# TeensyBreakoutBoard.net
KiCad netlist of a schematic drawn in EAGLE
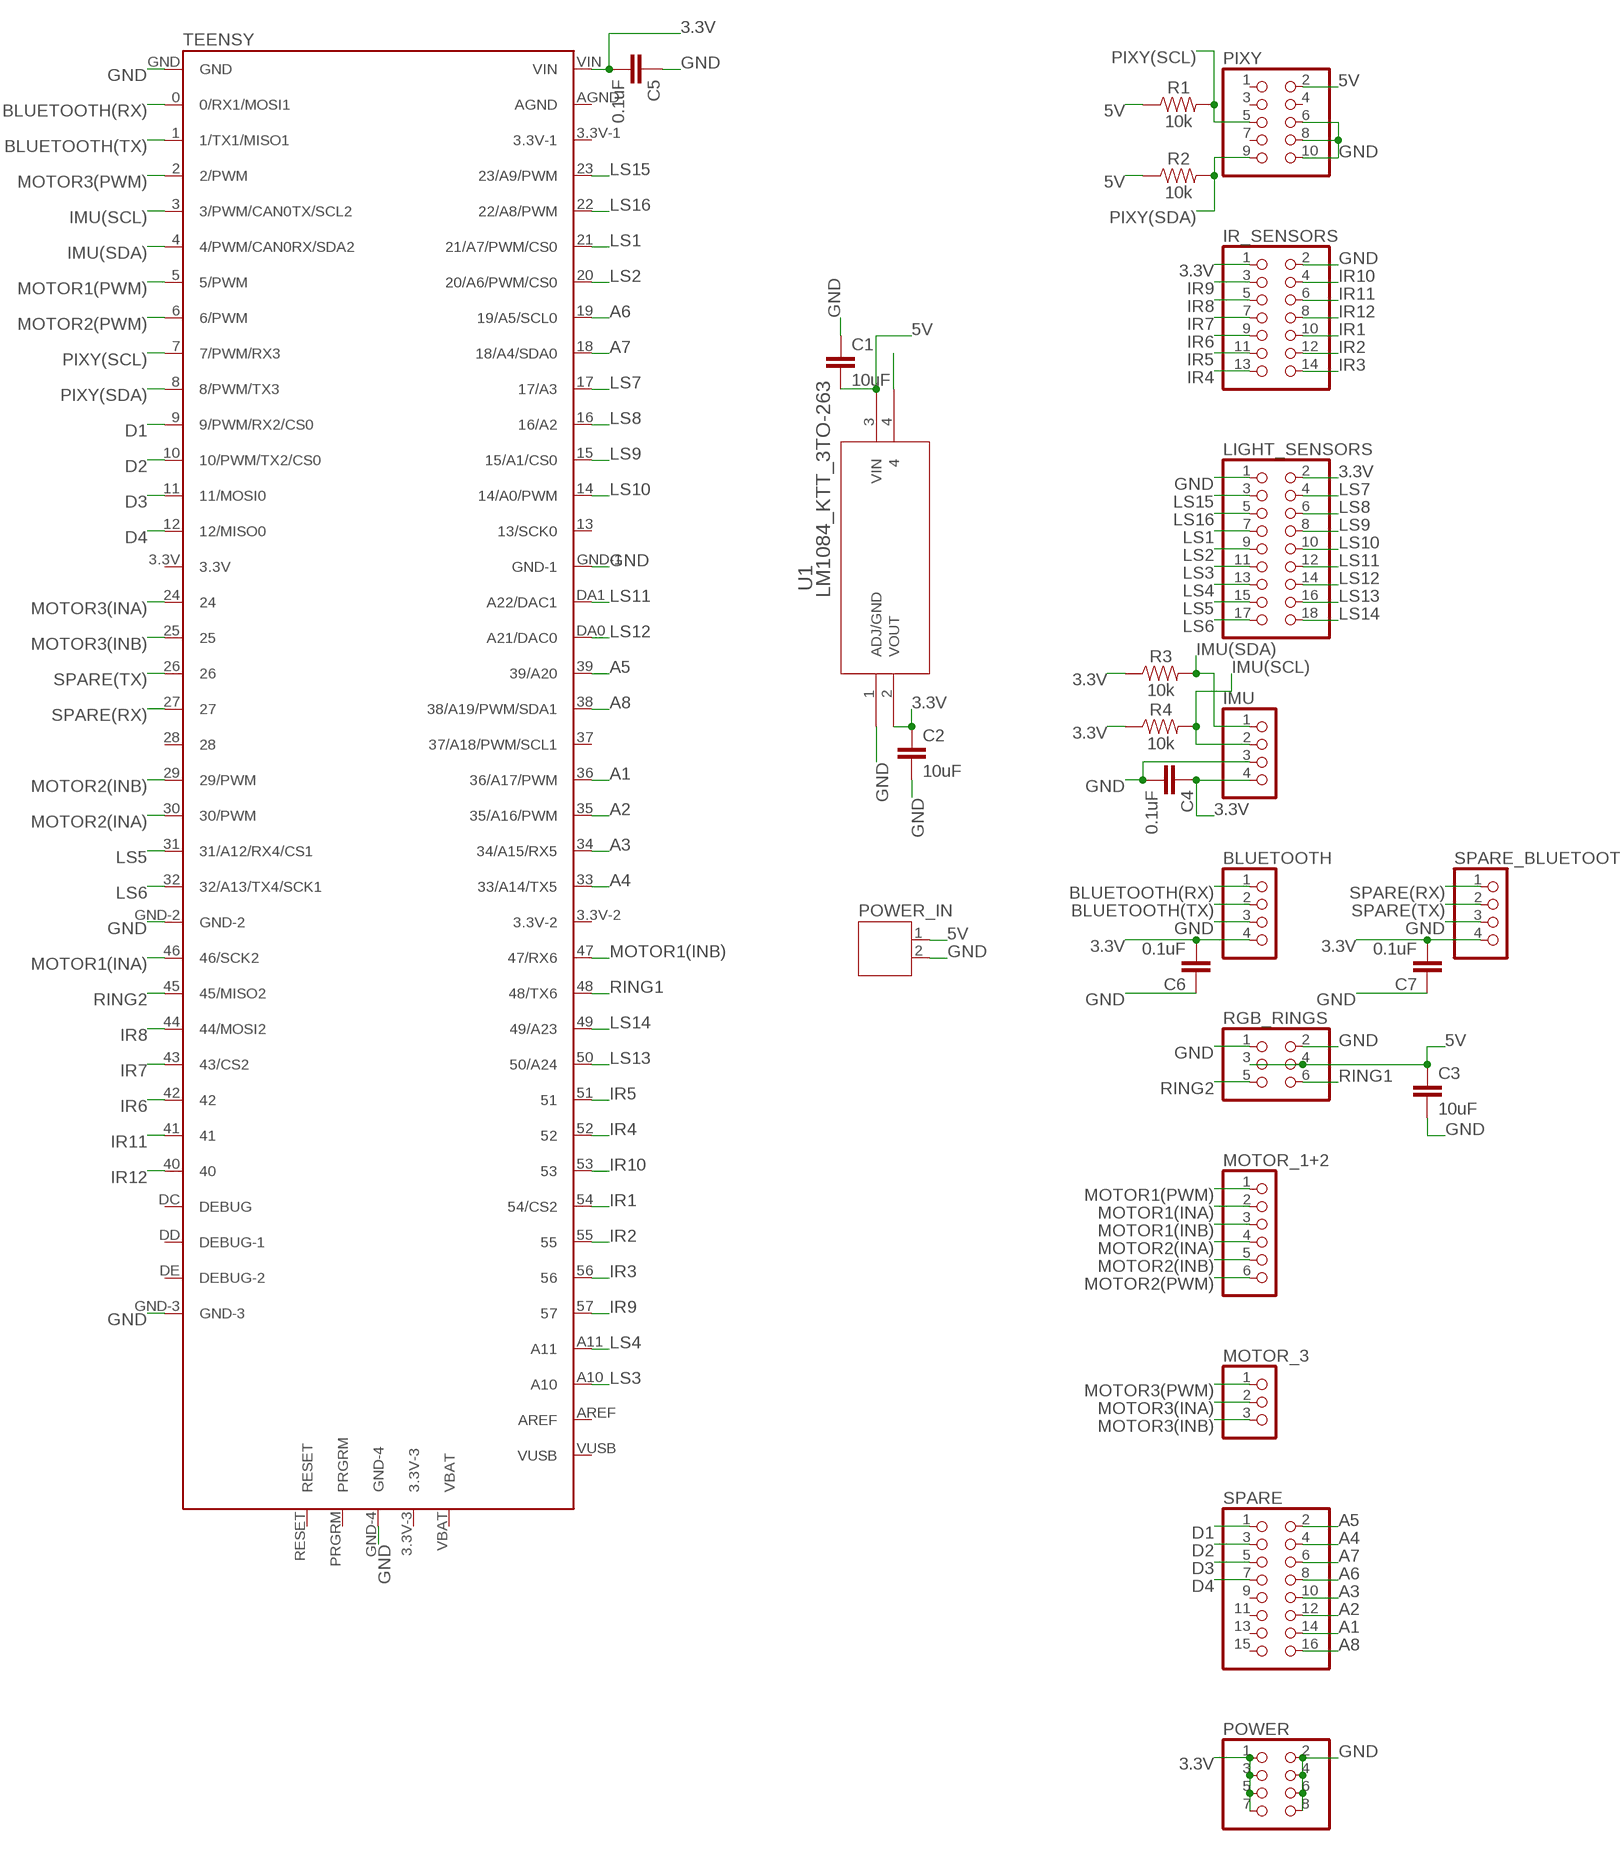
[diagram p0: schematic, sheet 1]

(export (version "E")
  (design (tool "Eeschema 10.0.6"))
  (components
    (comp (ref "BLUETOOTH")
      (value "PINHD-1X4")
      (footprint "eagle-import:1X04")
      (libsource (lib "eagle-import") (part "PINHD-1X4"))
    )
    (comp (ref "C1")
      (value "10uF")
      (footprint "eagle-import:0805")
      (libsource (lib "eagle-import") (part "10UF-0805-10V-10%"))
    )
    (comp (ref "C2")
      (value "10uF")
      (footprint "eagle-import:0805")
      (libsource (lib "eagle-import") (part "10UF-0805-10V-10%"))
    )
    (comp (ref "C3")
      (value "10uF")
      (footprint "eagle-import:0805")
      (libsource (lib "eagle-import") (part "10UF-0805-10V-10%"))
    )
    (comp (ref "C4")
      (value "0.1uF")
      (footprint "eagle-import:0603")
      (libsource (lib "eagle-import") (part "0.1UF-0603-25V-(+80/-20%)"))
    )
    (comp (ref "C5")
      (value "0.1uF")
      (footprint "eagle-import:0603")
      (libsource (lib "eagle-import") (part "0.1UF-0603-25V-(+80/-20%)"))
    )
    (comp (ref "C6")
      (value "0.1uF")
      (footprint "eagle-import:0603")
      (libsource (lib "eagle-import") (part "0.1UF-0603-25V-(+80/-20%)"))
    )
    (comp (ref "C7")
      (value "0.1uF")
      (footprint "eagle-import:0603")
      (libsource (lib "eagle-import") (part "0.1UF-0603-25V-(+80/-20%)"))
    )
    (comp (ref "IMU")
      (value "PINHD-1X4")
      (footprint "eagle-import:1X04")
      (libsource (lib "eagle-import") (part "PINHD-1X4"))
    )
    (comp (ref "IR_SENSORS")
      (value "PINHD-2X7")
      (footprint "eagle-import:2X07")
      (libsource (lib "eagle-import") (part "PINHD-2X7"))
    )
    (comp (ref "LIGHT_SENSORS")
      (value "PINHD-2X9")
      (footprint "eagle-import:2X09")
      (libsource (lib "eagle-import") (part "PINHD-2X9"))
    )
    (comp (ref "MOTOR_1+2")
      (value "PINHD-1X6")
      (footprint "eagle-import:1X06")
      (libsource (lib "eagle-import") (part "PINHD-1X6"))
    )
    (comp (ref "MOTOR_3")
      (value "PINHD-1X3")
      (footprint "eagle-import:1X03")
      (libsource (lib "eagle-import") (part "PINHD-1X3"))
    )
    (comp (ref "PIXY")
      (value "PINHD-2X5")
      (footprint "eagle-import:2X05")
      (libsource (lib "eagle-import") (part "PINHD-2X5"))
    )
    (comp (ref "POWER")
      (value "PINHD-2X4")
      (footprint "eagle-import:2X04")
      (libsource (lib "eagle-import") (part "PINHD-2X4"))
    )
    (comp (ref "POWER_IN")
      (value "JST-PH2")
      (footprint "eagle-import:JST-PH2")
      (libsource (lib "eagle-import") (part "JST-PH2"))
    )
    (comp (ref "R1")
      (value "10k")
      (footprint "eagle-import:0603")
      (libsource (lib "eagle-import") (part "10KOHM-0603-1/10W-1%"))
    )
    (comp (ref "R2")
      (value "10k")
      (footprint "eagle-import:0603")
      (libsource (lib "eagle-import") (part "10KOHM-0603-1/10W-1%"))
    )
    (comp (ref "R3")
      (value "10k")
      (footprint "eagle-import:0603")
      (libsource (lib "eagle-import") (part "10KOHM-0603-1/10W-1%"))
    )
    (comp (ref "R4")
      (value "10k")
      (footprint "eagle-import:0603")
      (libsource (lib "eagle-import") (part "10KOHM-0603-1/10W-1%"))
    )
    (comp (ref "RGB_RINGS")
      (value "PINHD-2X3")
      (footprint "eagle-import:2X03")
      (libsource (lib "eagle-import") (part "PINHD-2X3"))
    )
    (comp (ref "SPARE")
      (value "PINHD-2X8")
      (footprint "eagle-import:2X08")
      (libsource (lib "eagle-import") (part "PINHD-2X8"))
    )
    (comp (ref "SPARE_BLUETOOTH")
      (value "PINHD-1X4")
      (footprint "eagle-import:1X04")
      (libsource (lib "eagle-import") (part "PINHD-1X4"))
    )
    (comp (ref "TEENSY")
      (value "TEENSY-3.5")
      (footprint "eagle-import:TEENSY-3.5")
      (libsource (lib "eagle-import") (part "TEENSY-3.5"))
    )
    (comp (ref "U1")
      (value "LM1084_KTT_3TO-263")
      (footprint "eagle-import:TS3B")
      (fields (field (name "PARTNUMBER") "LM1084IS-33"))
      (libsource (lib "eagle-import") (part "LM1084_KTT_3TO-263"))
    )
  )
  (nets
    (net (code "1") (name "/3.3V") (class "Default")
      (node (ref "BLUETOOTH") (pin "4") (pinfunction "4_4") (pintype "passive"))
      (node (ref "C2") (pin "1") (pinfunction "1_1") (pintype "passive"))
      (node (ref "C4") (pin "1") (pinfunction "1_1") (pintype "passive"))
      (node (ref "C5") (pin "2") (pinfunction "2_2") (pintype "passive"))
      (node (ref "C6") (pin "2") (pinfunction "2_2") (pintype "passive"))
      (node (ref "C7") (pin "2") (pinfunction "2_2") (pintype "passive"))
      (node (ref "IMU") (pin "4") (pinfunction "4_4") (pintype "passive"))
      (node (ref "IR_SENSORS") (pin "1") (pinfunction "1_1") (pintype "passive"))
      (node (ref "LIGHT_SENSORS") (pin "2") (pinfunction "2_2") (pintype "passive"))
      (node (ref "POWER") (pin "1") (pinfunction "1_1") (pintype "passive"))
      (node (ref "POWER") (pin "3") (pinfunction "3_3") (pintype "passive"))
      (node (ref "POWER") (pin "5") (pinfunction "5_5") (pintype "passive"))
      (node (ref "POWER") (pin "7") (pinfunction "7_7") (pintype "passive"))
      (node (ref "R3") (pin "1") (pinfunction "1_1") (pintype "passive"))
      (node (ref "R4") (pin "1") (pinfunction "1_1") (pintype "passive"))
      (node (ref "SPARE_BLUETOOTH") (pin "4") (pinfunction "4_4") (pintype "passive"))
      (node (ref "TEENSY") (pin "VIN") (pinfunction "VIN_VIN") (pintype "bidirectional"))
      (node (ref "U1") (pin "2") (pinfunction "VOUT_2") (pintype "output"))
    )
    (net (code "2") (name "/5V") (class "Default")
      (node (ref "C1") (pin "2") (pinfunction "2_2") (pintype "passive"))
      (node (ref "C3") (pin "1") (pinfunction "1_1") (pintype "passive"))
      (node (ref "PIXY") (pin "2") (pinfunction "2_2") (pintype "passive"))
      (node (ref "POWER_IN") (pin "1") (pinfunction "1_1") (pintype "passive"))
      (node (ref "R1") (pin "1") (pinfunction "1_1") (pintype "passive"))
      (node (ref "R2") (pin "1") (pinfunction "1_1") (pintype "passive"))
      (node (ref "RGB_RINGS") (pin "3") (pinfunction "3_3") (pintype "passive"))
      (node (ref "RGB_RINGS") (pin "4") (pinfunction "4_4") (pintype "passive"))
      (node (ref "U1") (pin "3") (pinfunction "VIN_3") (pintype "input"))
    )
    (net (code "3") (name "/A1") (class "Default")
      (node (ref "SPARE") (pin "14") (pinfunction "14_14") (pintype "passive"))
      (node (ref "TEENSY") (pin "36") (pinfunction "36/A17/PWM_36") (pintype "bidirectional"))
    )
    (net (code "4") (name "/A2") (class "Default")
      (node (ref "SPARE") (pin "12") (pinfunction "12_12") (pintype "passive"))
      (node (ref "TEENSY") (pin "35") (pinfunction "35/A16/PWM_35") (pintype "bidirectional"))
    )
    (net (code "5") (name "/A3") (class "Default")
      (node (ref "SPARE") (pin "10") (pinfunction "10_10") (pintype "passive"))
      (node (ref "TEENSY") (pin "34") (pinfunction "34/A15/RX5_34") (pintype "bidirectional"))
    )
    (net (code "6") (name "/A4") (class "Default")
      (node (ref "SPARE") (pin "4") (pinfunction "4_4") (pintype "passive"))
      (node (ref "TEENSY") (pin "33") (pinfunction "33/A14/TX5_33") (pintype "bidirectional"))
    )
    (net (code "7") (name "/A5") (class "Default")
      (node (ref "SPARE") (pin "2") (pinfunction "2_2") (pintype "passive"))
      (node (ref "TEENSY") (pin "39") (pinfunction "39/A20_39") (pintype "bidirectional"))
    )
    (net (code "8") (name "/A6") (class "Default")
      (node (ref "SPARE") (pin "8") (pinfunction "8_8") (pintype "passive"))
      (node (ref "TEENSY") (pin "19") (pinfunction "19/A5/SCL0_19") (pintype "bidirectional"))
    )
    (net (code "9") (name "/A7") (class "Default")
      (node (ref "SPARE") (pin "6") (pinfunction "6_6") (pintype "passive"))
      (node (ref "TEENSY") (pin "18") (pinfunction "18/A4/SDA0_18") (pintype "bidirectional"))
    )
    (net (code "10") (name "/A8") (class "Default")
      (node (ref "SPARE") (pin "16") (pinfunction "16_16") (pintype "passive"))
      (node (ref "TEENSY") (pin "38") (pinfunction "38/A19/PWM/SDA1_38") (pintype "bidirectional"))
    )
    (net (code "11") (name "/BLUETOOTH(RX)") (class "Default")
      (node (ref "BLUETOOTH") (pin "1") (pinfunction "1_1") (pintype "passive"))
      (node (ref "TEENSY") (pin "0") (pinfunction "0/RX1/MOSI1_0") (pintype "bidirectional"))
    )
    (net (code "12") (name "/BLUETOOTH(TX)") (class "Default")
      (node (ref "BLUETOOTH") (pin "2") (pinfunction "2_2") (pintype "passive"))
      (node (ref "TEENSY") (pin "1") (pinfunction "1/TX1/MISO1_1") (pintype "bidirectional"))
    )
    (net (code "13") (name "/D1") (class "Default")
      (node (ref "SPARE") (pin "1") (pinfunction "1_1") (pintype "passive"))
      (node (ref "TEENSY") (pin "9") (pinfunction "9/PWM/RX2/CS0_9") (pintype "bidirectional"))
    )
    (net (code "14") (name "/D2") (class "Default")
      (node (ref "SPARE") (pin "3") (pinfunction "3_3") (pintype "passive"))
      (node (ref "TEENSY") (pin "10") (pinfunction "10/PWM/TX2/CS0_10") (pintype "bidirectional"))
    )
    (net (code "15") (name "/D3") (class "Default")
      (node (ref "SPARE") (pin "5") (pinfunction "5_5") (pintype "passive"))
      (node (ref "TEENSY") (pin "11") (pinfunction "11/MOSI0_11") (pintype "bidirectional"))
    )
    (net (code "16") (name "/D4") (class "Default")
      (node (ref "SPARE") (pin "7") (pinfunction "7_7") (pintype "passive"))
      (node (ref "TEENSY") (pin "12") (pinfunction "12/MISO0_12") (pintype "bidirectional"))
    )
    (net (code "17") (name "/GND") (class "Default")
      (node (ref "BLUETOOTH") (pin "3") (pinfunction "3_3") (pintype "passive"))
      (node (ref "C1") (pin "1") (pinfunction "1_1") (pintype "passive"))
      (node (ref "C2") (pin "2") (pinfunction "2_2") (pintype "passive"))
      (node (ref "C3") (pin "2") (pinfunction "2_2") (pintype "passive"))
      (node (ref "C4") (pin "2") (pinfunction "2_2") (pintype "passive"))
      (node (ref "C5") (pin "1") (pinfunction "1_1") (pintype "passive"))
      (node (ref "C6") (pin "1") (pinfunction "1_1") (pintype "passive"))
      (node (ref "C7") (pin "1") (pinfunction "1_1") (pintype "passive"))
      (node (ref "IMU") (pin "3") (pinfunction "3_3") (pintype "passive"))
      (node (ref "IR_SENSORS") (pin "2") (pinfunction "2_2") (pintype "passive"))
      (node (ref "LIGHT_SENSORS") (pin "1") (pinfunction "1_1") (pintype "passive"))
      (node (ref "PIXY") (pin "10") (pinfunction "10_10") (pintype "passive"))
      (node (ref "PIXY") (pin "6") (pinfunction "6_6") (pintype "passive"))
      (node (ref "PIXY") (pin "8") (pinfunction "8_8") (pintype "passive"))
      (node (ref "POWER") (pin "2") (pinfunction "2_2") (pintype "passive"))
      (node (ref "POWER") (pin "4") (pinfunction "4_4") (pintype "passive"))
      (node (ref "POWER") (pin "6") (pinfunction "6_6") (pintype "passive"))
      (node (ref "POWER") (pin "8") (pinfunction "8_8") (pintype "passive"))
      (node (ref "POWER_IN") (pin "2") (pinfunction "2_2") (pintype "passive"))
      (node (ref "RGB_RINGS") (pin "1") (pinfunction "1_1") (pintype "passive"))
      (node (ref "RGB_RINGS") (pin "2") (pinfunction "2_2") (pintype "passive"))
      (node (ref "SPARE_BLUETOOTH") (pin "3") (pinfunction "3_3") (pintype "passive"))
      (node (ref "TEENSY") (pin "GND") (pinfunction "GND_GND") (pintype "bidirectional"))
      (node (ref "TEENSY") (pin "GND-1") (pinfunction "GND-1_GND-1") (pintype "bidirectional"))
      (node (ref "TEENSY") (pin "GND-2") (pinfunction "GND-2_GND-2") (pintype "bidirectional"))
      (node (ref "TEENSY") (pin "GND-3") (pinfunction "GND-3_GND-3") (pintype "bidirectional"))
      (node (ref "TEENSY") (pin "GND-4") (pinfunction "GND-4_GND-4") (pintype "bidirectional"))
      (node (ref "U1") (pin "1") (pinfunction "ADJ/GND_1") (pintype "passive"))
    )
    (net (code "18") (name "/IMU(SCL)") (class "Default")
      (node (ref "IMU") (pin "2") (pinfunction "2_2") (pintype "passive"))
      (node (ref "R4") (pin "2") (pinfunction "2_2") (pintype "passive"))
      (node (ref "TEENSY") (pin "3") (pinfunction "3/PWM/CAN0TX/SCL2_3") (pintype "bidirectional"))
    )
    (net (code "19") (name "/IMU(SDA)") (class "Default")
      (node (ref "IMU") (pin "1") (pinfunction "1_1") (pintype "passive"))
      (node (ref "R3") (pin "2") (pinfunction "2_2") (pintype "passive"))
      (node (ref "TEENSY") (pin "4") (pinfunction "4/PWM/CAN0RX/SDA2_4") (pintype "bidirectional"))
    )
    (net (code "20") (name "/IR1") (class "Default")
      (node (ref "IR_SENSORS") (pin "10") (pinfunction "10_10") (pintype "passive"))
      (node (ref "TEENSY") (pin "54") (pinfunction "54/CS2_54") (pintype "bidirectional"))
    )
    (net (code "21") (name "/IR2") (class "Default")
      (node (ref "IR_SENSORS") (pin "12") (pinfunction "12_12") (pintype "passive"))
      (node (ref "TEENSY") (pin "55") (pinfunction "55_55") (pintype "bidirectional"))
    )
    (net (code "22") (name "/IR3") (class "Default")
      (node (ref "IR_SENSORS") (pin "14") (pinfunction "14_14") (pintype "passive"))
      (node (ref "TEENSY") (pin "56") (pinfunction "56_56") (pintype "bidirectional"))
    )
    (net (code "23") (name "/IR4") (class "Default")
      (node (ref "IR_SENSORS") (pin "13") (pinfunction "13_13") (pintype "passive"))
      (node (ref "TEENSY") (pin "52") (pinfunction "52_52") (pintype "bidirectional"))
    )
    (net (code "24") (name "/IR5") (class "Default")
      (node (ref "IR_SENSORS") (pin "11") (pinfunction "11_11") (pintype "passive"))
      (node (ref "TEENSY") (pin "51") (pinfunction "51_51") (pintype "bidirectional"))
    )
    (net (code "25") (name "/IR6") (class "Default")
      (node (ref "IR_SENSORS") (pin "9") (pinfunction "9_9") (pintype "passive"))
      (node (ref "TEENSY") (pin "42") (pinfunction "42_42") (pintype "bidirectional"))
    )
    (net (code "26") (name "/IR7") (class "Default")
      (node (ref "IR_SENSORS") (pin "7") (pinfunction "7_7") (pintype "passive"))
      (node (ref "TEENSY") (pin "43") (pinfunction "43/CS2_43") (pintype "bidirectional"))
    )
    (net (code "27") (name "/IR8") (class "Default")
      (node (ref "IR_SENSORS") (pin "5") (pinfunction "5_5") (pintype "passive"))
      (node (ref "TEENSY") (pin "44") (pinfunction "44/MOSI2_44") (pintype "bidirectional"))
    )
    (net (code "28") (name "/IR9") (class "Default")
      (node (ref "IR_SENSORS") (pin "3") (pinfunction "3_3") (pintype "passive"))
      (node (ref "TEENSY") (pin "57") (pinfunction "57_57") (pintype "bidirectional"))
    )
    (net (code "29") (name "/IR10") (class "Default")
      (node (ref "IR_SENSORS") (pin "4") (pinfunction "4_4") (pintype "passive"))
      (node (ref "TEENSY") (pin "53") (pinfunction "53_53") (pintype "bidirectional"))
    )
    (net (code "30") (name "/IR11") (class "Default")
      (node (ref "IR_SENSORS") (pin "6") (pinfunction "6_6") (pintype "passive"))
      (node (ref "TEENSY") (pin "41") (pinfunction "41_41") (pintype "bidirectional"))
    )
    (net (code "31") (name "/IR12") (class "Default")
      (node (ref "IR_SENSORS") (pin "8") (pinfunction "8_8") (pintype "passive"))
      (node (ref "TEENSY") (pin "40") (pinfunction "40_40") (pintype "bidirectional"))
    )
    (net (code "32") (name "/LS1") (class "Default")
      (node (ref "LIGHT_SENSORS") (pin "7") (pinfunction "7_7") (pintype "passive"))
      (node (ref "TEENSY") (pin "21") (pinfunction "21/A7/PWM/CS0_21") (pintype "bidirectional"))
    )
    (net (code "33") (name "/LS2") (class "Default")
      (node (ref "LIGHT_SENSORS") (pin "9") (pinfunction "9_9") (pintype "passive"))
      (node (ref "TEENSY") (pin "20") (pinfunction "20/A6/PWM/CS0_20") (pintype "bidirectional"))
    )
    (net (code "34") (name "/LS3") (class "Default")
      (node (ref "LIGHT_SENSORS") (pin "11") (pinfunction "11_11") (pintype "passive"))
      (node (ref "TEENSY") (pin "A10") (pinfunction "A10_A10") (pintype "bidirectional"))
    )
    (net (code "35") (name "/LS4") (class "Default")
      (node (ref "LIGHT_SENSORS") (pin "13") (pinfunction "13_13") (pintype "passive"))
      (node (ref "TEENSY") (pin "A11") (pinfunction "A11_A11") (pintype "bidirectional"))
    )
    (net (code "36") (name "/LS5") (class "Default")
      (node (ref "LIGHT_SENSORS") (pin "15") (pinfunction "15_15") (pintype "passive"))
      (node (ref "TEENSY") (pin "31") (pinfunction "31/A12/RX4/CS1_31") (pintype "bidirectional"))
    )
    (net (code "37") (name "/LS6") (class "Default")
      (node (ref "LIGHT_SENSORS") (pin "17") (pinfunction "17_17") (pintype "passive"))
      (node (ref "TEENSY") (pin "32") (pinfunction "32/A13/TX4/SCK1_32") (pintype "bidirectional"))
    )
    (net (code "38") (name "/LS7") (class "Default")
      (node (ref "LIGHT_SENSORS") (pin "4") (pinfunction "4_4") (pintype "passive"))
      (node (ref "TEENSY") (pin "17") (pinfunction "17/A3_17") (pintype "bidirectional"))
    )
    (net (code "39") (name "/LS8") (class "Default")
      (node (ref "LIGHT_SENSORS") (pin "6") (pinfunction "6_6") (pintype "passive"))
      (node (ref "TEENSY") (pin "16") (pinfunction "16/A2_16") (pintype "bidirectional"))
    )
    (net (code "40") (name "/LS9") (class "Default")
      (node (ref "LIGHT_SENSORS") (pin "8") (pinfunction "8_8") (pintype "passive"))
      (node (ref "TEENSY") (pin "15") (pinfunction "15/A1/CS0_15") (pintype "bidirectional"))
    )
    (net (code "41") (name "/LS10") (class "Default")
      (node (ref "LIGHT_SENSORS") (pin "10") (pinfunction "10_10") (pintype "passive"))
      (node (ref "TEENSY") (pin "14") (pinfunction "14/A0/PWM_14") (pintype "bidirectional"))
    )
    (net (code "42") (name "/LS11") (class "Default")
      (node (ref "LIGHT_SENSORS") (pin "12") (pinfunction "12_12") (pintype "passive"))
      (node (ref "TEENSY") (pin "DA1") (pinfunction "A22/DAC1_DA1") (pintype "bidirectional"))
    )
    (net (code "43") (name "/LS12") (class "Default")
      (node (ref "LIGHT_SENSORS") (pin "14") (pinfunction "14_14") (pintype "passive"))
      (node (ref "TEENSY") (pin "DA0") (pinfunction "A21/DAC0_DA0") (pintype "bidirectional"))
    )
    (net (code "44") (name "/LS13") (class "Default")
      (node (ref "LIGHT_SENSORS") (pin "16") (pinfunction "16_16") (pintype "passive"))
      (node (ref "TEENSY") (pin "50") (pinfunction "50/A24_50") (pintype "bidirectional"))
    )
    (net (code "45") (name "/LS14") (class "Default")
      (node (ref "LIGHT_SENSORS") (pin "18") (pinfunction "18_18") (pintype "passive"))
      (node (ref "TEENSY") (pin "49") (pinfunction "49/A23_49") (pintype "bidirectional"))
    )
    (net (code "46") (name "/LS15") (class "Default")
      (node (ref "LIGHT_SENSORS") (pin "3") (pinfunction "3_3") (pintype "passive"))
      (node (ref "TEENSY") (pin "23") (pinfunction "23/A9/PWM_23") (pintype "bidirectional"))
    )
    (net (code "47") (name "/LS16") (class "Default")
      (node (ref "LIGHT_SENSORS") (pin "5") (pinfunction "5_5") (pintype "passive"))
      (node (ref "TEENSY") (pin "22") (pinfunction "22/A8/PWM_22") (pintype "bidirectional"))
    )
    (net (code "48") (name "/MOTOR1(INA)") (class "Default")
      (node (ref "MOTOR_1+2") (pin "2") (pinfunction "2_2") (pintype "passive"))
      (node (ref "TEENSY") (pin "46") (pinfunction "46/SCK2_46") (pintype "bidirectional"))
    )
    (net (code "49") (name "/MOTOR1(INB)") (class "Default")
      (node (ref "MOTOR_1+2") (pin "3") (pinfunction "3_3") (pintype "passive"))
      (node (ref "TEENSY") (pin "47") (pinfunction "47/RX6_47") (pintype "bidirectional"))
    )
    (net (code "50") (name "/MOTOR1(PWM)") (class "Default")
      (node (ref "MOTOR_1+2") (pin "1") (pinfunction "1_1") (pintype "passive"))
      (node (ref "TEENSY") (pin "5") (pinfunction "5/PWM_5") (pintype "bidirectional"))
    )
    (net (code "51") (name "/MOTOR2(INA)") (class "Default")
      (node (ref "MOTOR_1+2") (pin "4") (pinfunction "4_4") (pintype "passive"))
      (node (ref "TEENSY") (pin "30") (pinfunction "30/PWM_30") (pintype "bidirectional"))
    )
    (net (code "52") (name "/MOTOR2(INB)") (class "Default")
      (node (ref "MOTOR_1+2") (pin "5") (pinfunction "5_5") (pintype "passive"))
      (node (ref "TEENSY") (pin "29") (pinfunction "29/PWM_29") (pintype "bidirectional"))
    )
    (net (code "53") (name "/MOTOR2(PWM)") (class "Default")
      (node (ref "MOTOR_1+2") (pin "6") (pinfunction "6_6") (pintype "passive"))
      (node (ref "TEENSY") (pin "6") (pinfunction "6/PWM_6") (pintype "bidirectional"))
    )
    (net (code "54") (name "/MOTOR3(INA)") (class "Default")
      (node (ref "MOTOR_3") (pin "2") (pinfunction "2_2") (pintype "passive"))
      (node (ref "TEENSY") (pin "24") (pinfunction "24_24") (pintype "bidirectional"))
    )
    (net (code "55") (name "/MOTOR3(INB)") (class "Default")
      (node (ref "MOTOR_3") (pin "3") (pinfunction "3_3") (pintype "passive"))
      (node (ref "TEENSY") (pin "25") (pinfunction "25_25") (pintype "bidirectional"))
    )
    (net (code "56") (name "/MOTOR3(PWM)") (class "Default")
      (node (ref "MOTOR_3") (pin "1") (pinfunction "1_1") (pintype "passive"))
      (node (ref "TEENSY") (pin "2") (pinfunction "2/PWM_2") (pintype "bidirectional"))
    )
    (net (code "57") (name "/PIXY(SCL)") (class "Default")
      (node (ref "PIXY") (pin "5") (pinfunction "5_5") (pintype "passive"))
      (node (ref "R1") (pin "2") (pinfunction "2_2") (pintype "passive"))
      (node (ref "TEENSY") (pin "7") (pinfunction "7/PWM/RX3_7") (pintype "bidirectional"))
    )
    (net (code "58") (name "/PIXY(SDA)") (class "Default")
      (node (ref "PIXY") (pin "9") (pinfunction "9_9") (pintype "passive"))
      (node (ref "R2") (pin "2") (pinfunction "2_2") (pintype "passive"))
      (node (ref "TEENSY") (pin "8") (pinfunction "8/PWM/TX3_8") (pintype "bidirectional"))
    )
    (net (code "59") (name "/RING1") (class "Default")
      (node (ref "RGB_RINGS") (pin "6") (pinfunction "6_6") (pintype "passive"))
      (node (ref "TEENSY") (pin "48") (pinfunction "48/TX6_48") (pintype "bidirectional"))
    )
    (net (code "60") (name "/RING2") (class "Default")
      (node (ref "RGB_RINGS") (pin "5") (pinfunction "5_5") (pintype "passive"))
      (node (ref "TEENSY") (pin "45") (pinfunction "45/MISO2_45") (pintype "bidirectional"))
    )
    (net (code "61") (name "/SPARE(RX)") (class "Default")
      (node (ref "SPARE_BLUETOOTH") (pin "1") (pinfunction "1_1") (pintype "passive"))
      (node (ref "TEENSY") (pin "27") (pinfunction "27_27") (pintype "bidirectional"))
    )
    (net (code "62") (name "/SPARE(TX)") (class "Default")
      (node (ref "SPARE_BLUETOOTH") (pin "2") (pinfunction "2_2") (pintype "passive"))
      (node (ref "TEENSY") (pin "26") (pinfunction "26_26") (pintype "bidirectional"))
    )
    (net (code "63") (name "unconnected-(PIXY-Pad1)") (class "Default")
      (node (ref "PIXY") (pin "1") (pinfunction "1_1") (pintype "passive"))
    )
    (net (code "64") (name "unconnected-(PIXY-Pad3)") (class "Default")
      (node (ref "PIXY") (pin "3") (pinfunction "3_3") (pintype "passive"))
    )
    (net (code "65") (name "unconnected-(PIXY-Pad4)") (class "Default")
      (node (ref "PIXY") (pin "4") (pinfunction "4_4") (pintype "passive"))
    )
    (net (code "66") (name "unconnected-(PIXY-Pad7)") (class "Default")
      (node (ref "PIXY") (pin "7") (pinfunction "7_7") (pintype "passive"))
    )
    (net (code "67") (name "unconnected-(SPARE-Pad9)") (class "Default")
      (node (ref "SPARE") (pin "9") (pinfunction "9_9") (pintype "passive"))
    )
    (net (code "68") (name "unconnected-(SPARE-Pad11)") (class "Default")
      (node (ref "SPARE") (pin "11") (pinfunction "11_11") (pintype "passive"))
    )
    (net (code "69") (name "unconnected-(SPARE-Pad13)") (class "Default")
      (node (ref "SPARE") (pin "13") (pinfunction "13_13") (pintype "passive"))
    )
    (net (code "70") (name "unconnected-(SPARE-Pad15)") (class "Default")
      (node (ref "SPARE") (pin "15") (pinfunction "15_15") (pintype "passive"))
    )
    (net (code "71") (name "unconnected-(TEENSY-13{slash}SCK0-Pad13)") (class "Default")
      (node (ref "TEENSY") (pin "13") (pinfunction "13/SCK0_13") (pintype "bidirectional"))
    )
    (net (code "72") (name "unconnected-(TEENSY-37{slash}A18{slash}PWM{slash}SCL1-Pad37)") (class "Default")
      (node (ref "TEENSY") (pin "37") (pinfunction "37/A18/PWM/SCL1_37") (pintype "bidirectional"))
    )
    (net (code "73") (name "unconnected-(TEENSY-DEBUG-1-PadDD)") (class "Default")
      (node (ref "TEENSY") (pin "DD") (pinfunction "DEBUG-1_DD") (pintype "bidirectional"))
    )
    (net (code "74") (name "unconnected-(TEENSY-DEBUG-2-PadDE)") (class "Default")
      (node (ref "TEENSY") (pin "DE") (pinfunction "DEBUG-2_DE") (pintype "bidirectional"))
    )
    (net (code "75") (name "unconnected-(TEENSY-DEBUG-PadDC)") (class "Default")
      (node (ref "TEENSY") (pin "DC") (pinfunction "DEBUG_DC") (pintype "bidirectional"))
    )
    (net (code "76") (name "unconnected-(TEENSY-Pad3.3V)") (class "Default")
      (node (ref "TEENSY") (pin "3.3V") (pinfunction "3.3V_3.3V") (pintype "bidirectional"))
    )
    (net (code "77") (name "unconnected-(TEENSY-Pad3.3V-1)") (class "Default")
      (node (ref "TEENSY") (pin "3.3V-1") (pinfunction "3.3V-1_3.3V-1") (pintype "bidirectional"))
    )
    (net (code "78") (name "unconnected-(TEENSY-Pad3.3V-2)") (class "Default")
      (node (ref "TEENSY") (pin "3.3V-2") (pinfunction "3.3V-2_3.3V-2") (pintype "bidirectional"))
    )
    (net (code "79") (name "unconnected-(TEENSY-Pad3.3V-3)") (class "Default")
      (node (ref "TEENSY") (pin "3.3V-3") (pinfunction "3.3V-3_3.3V-3") (pintype "bidirectional"))
    )
    (net (code "80") (name "unconnected-(TEENSY-Pad28)") (class "Default")
      (node (ref "TEENSY") (pin "28") (pinfunction "28_28") (pintype "bidirectional"))
    )
    (net (code "81") (name "unconnected-(TEENSY-PadAGND)") (class "Default")
      (node (ref "TEENSY") (pin "AGND") (pinfunction "AGND_AGND") (pintype "bidirectional"))
    )
    (net (code "82") (name "unconnected-(TEENSY-PadAREF)") (class "Default")
      (node (ref "TEENSY") (pin "AREF") (pinfunction "AREF_AREF") (pintype "bidirectional"))
    )
    (net (code "83") (name "unconnected-(TEENSY-PadPRGRM)") (class "Default")
      (node (ref "TEENSY") (pin "PRGRM") (pinfunction "PRGRM_PRGRM") (pintype "bidirectional"))
    )
    (net (code "84") (name "unconnected-(TEENSY-PadRESET)") (class "Default")
      (node (ref "TEENSY") (pin "RESET") (pinfunction "RESET_RESET") (pintype "bidirectional"))
    )
    (net (code "85") (name "unconnected-(TEENSY-PadVBAT)") (class "Default")
      (node (ref "TEENSY") (pin "VBAT") (pinfunction "VBAT_VBAT") (pintype "bidirectional"))
    )
    (net (code "86") (name "unconnected-(TEENSY-PadVUSB)") (class "Default")
      (node (ref "TEENSY") (pin "VUSB") (pinfunction "VUSB_VUSB") (pintype "bidirectional"))
    )
    (net (code "87") (name "unconnected-(U1-Pad4)") (class "Default")
      (node (ref "U1") (pin "4") (pinfunction "4_4") (pintype "passive"))
    )
  )
)
